# DSO_Clock.net
KiCad netlist of a schematic drawn in Altium Designer
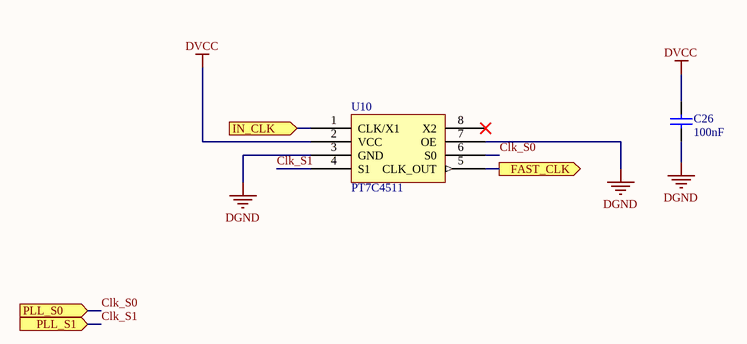
[diagram p0: DSO_Clock.SchDoc]

(export (version "E")
  (design (tool "Eeschema 10.0.6"))
  (components
    (comp (ref "C26")
      (value "100nF")
      (footprint "0805C")
      (description "Capacitor")
      (fields (field (name "REVIEWED BY") "RM - 2018/08/05"))
      (libsource (lib "DSO") (part "C"))
    )
    (comp (ref "U10")
      (value "PT7C4511")
      (footprint "SOIC-8")
      (description "PLL Clock Multiplier")
      (fields (field (name "REVIEWED BY") "RM - 2018/08/05"))
      (libsource (lib "DSO") (part "PT7C4511"))
    )
  )
  (nets
    (net (code "1") (name "/Clk_S0") (class "Default")
      (node (ref "U10") (pin "6") (pinfunction "S0_6") (pintype "passive"))
    )
    (net (code "2") (name "/Clk_S1") (class "Default")
      (node (ref "U10") (pin "4") (pinfunction "S1_4") (pintype "passive"))
    )
    (net (code "3") (name "/FAST_CLK") (class "Default")
      (node (ref "U10") (pin "5") (pinfunction "CLK_OUT_5") (pintype "output"))
    )
    (net (code "4") (name "/IN_CLK") (class "Default")
      (node (ref "U10") (pin "1") (pinfunction "CLK/X1_1") (pintype "passive"))
    )
    (net (code "5") (name "DGND") (class "Default")
      (node (ref "C26") (pin "2") (pinfunction "2_2") (pintype "passive"))
      (node (ref "U10") (pin "3") (pinfunction "GND_3") (pintype "passive"))
      (node (ref "U10") (pin "7") (pinfunction "OE_7") (pintype "passive"))
    )
    (net (code "6") (name "DVCC") (class "Default")
      (node (ref "C26") (pin "1") (pinfunction "1_1") (pintype "passive"))
      (node (ref "U10") (pin "2") (pinfunction "VCC_2") (pintype "passive"))
    )
    (net (code "7") (name "unconnected-(U10-X2-Pad8)") (class "Default")
      (node (ref "U10") (pin "8") (pinfunction "X2_8") (pintype "passive+no_connect"))
    )
  )
)
